# mcu.net
KiCad netlist of a schematic drawn in Altium Designer
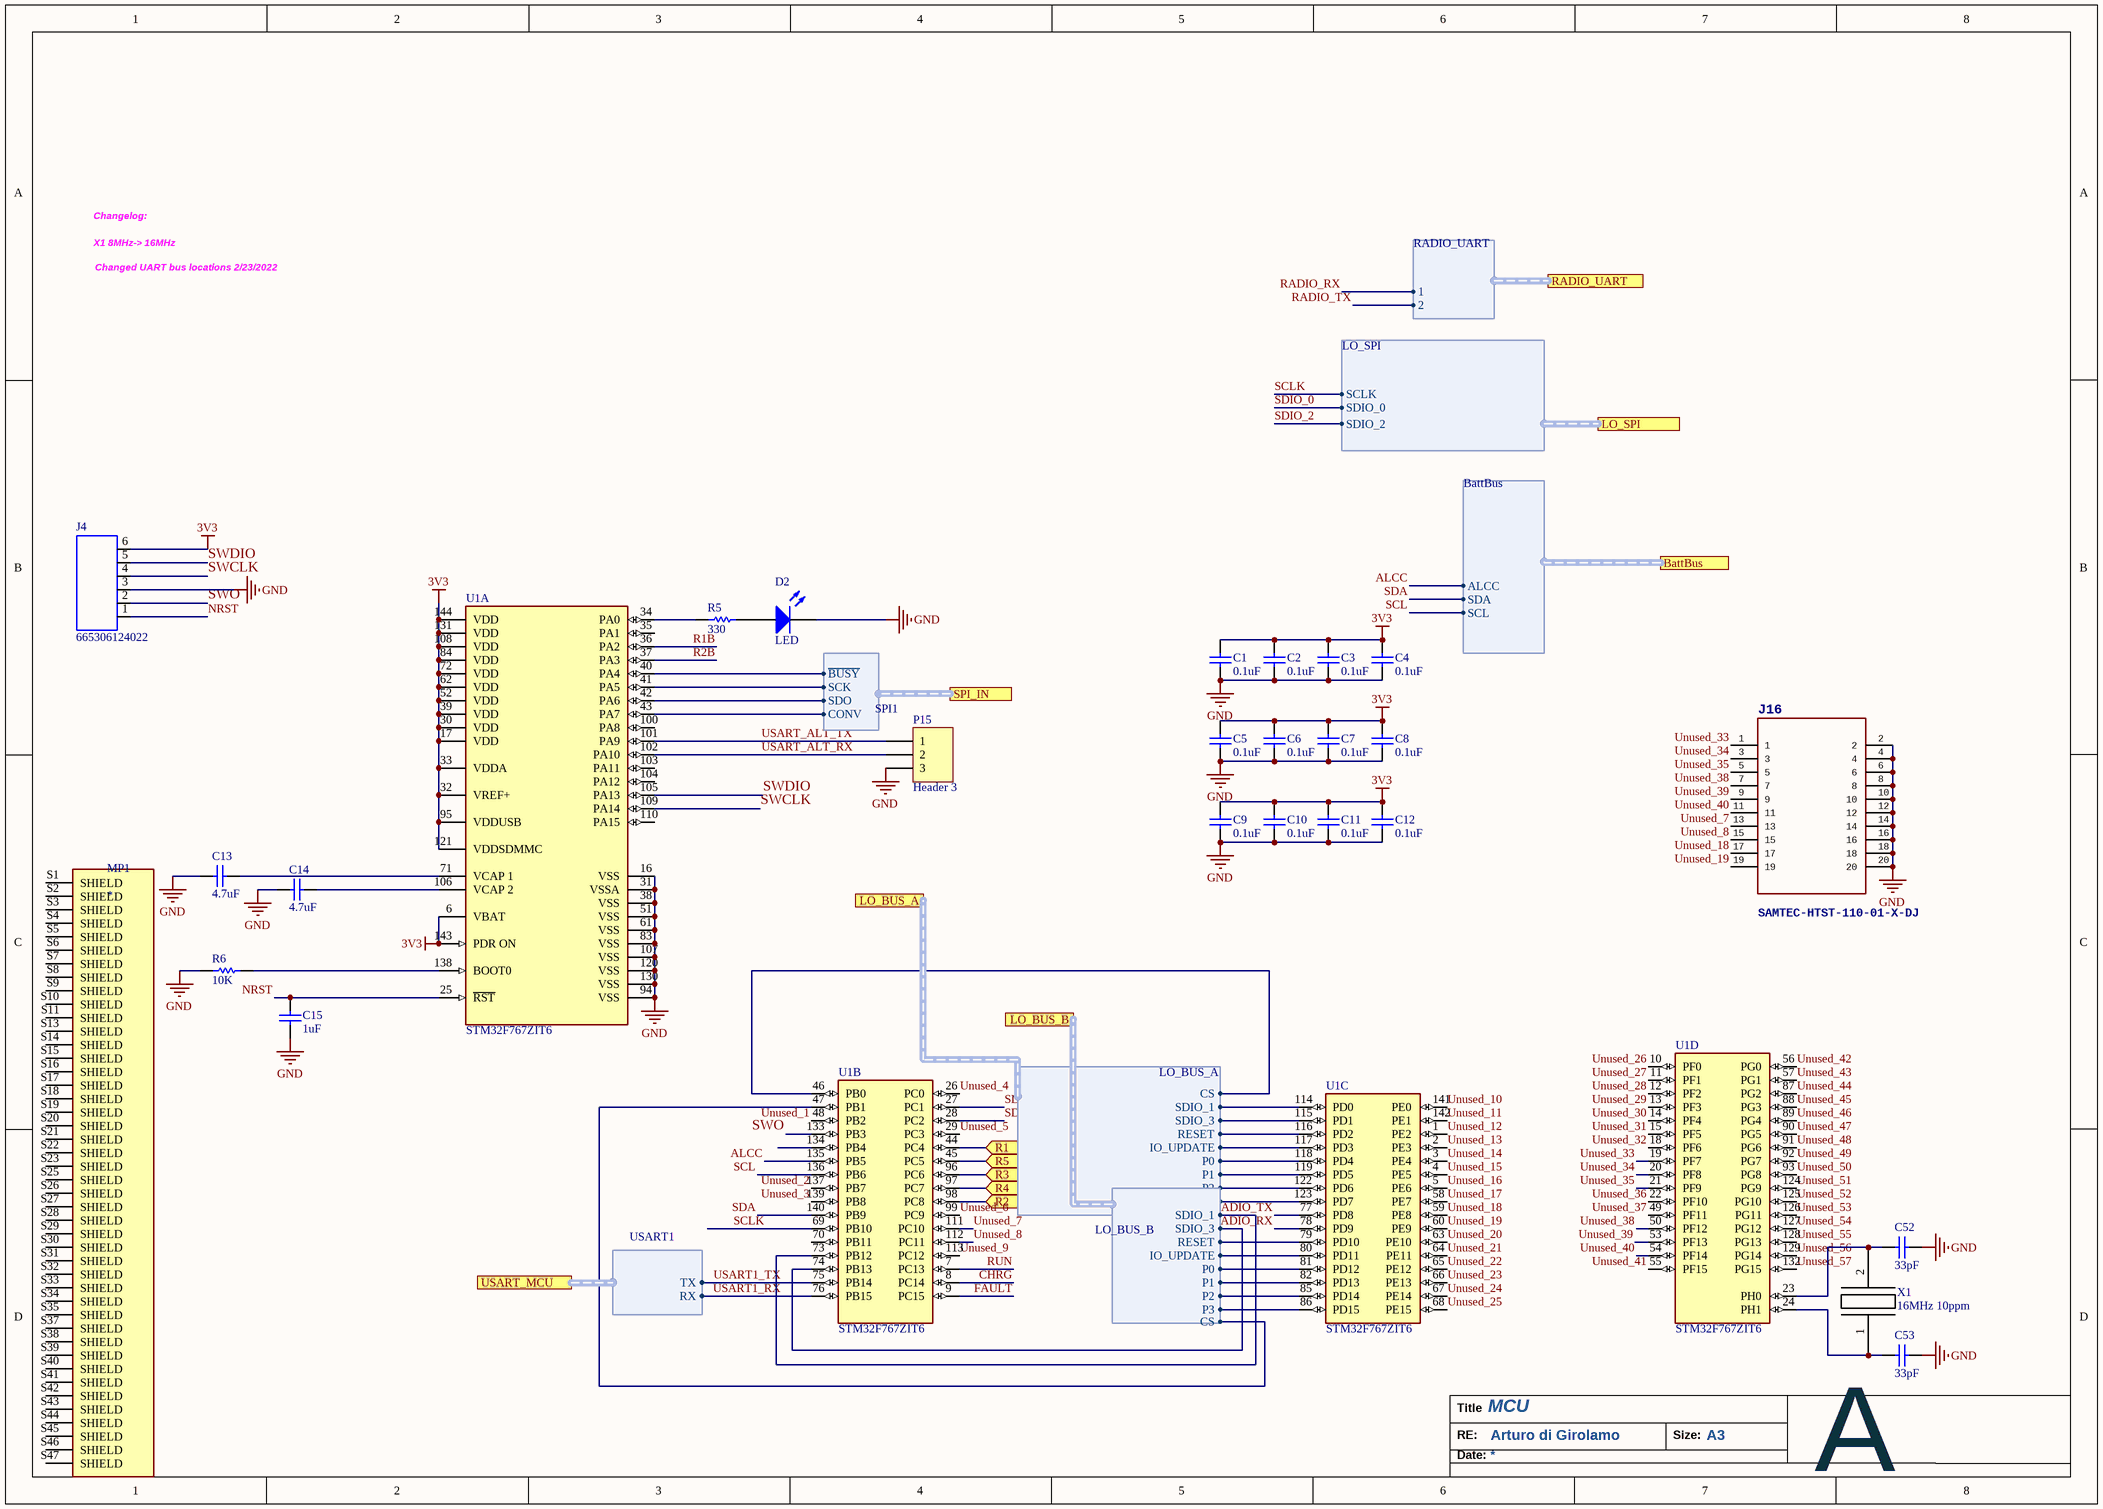
[diagram p0: mcu.SchDoc]

(export (version "E")
  (design (tool "Eeschema 10.0.6"))
  (components
    (comp (ref "C1")
      (value "0.1uF")
      (footprint "0402_Cap")
      (description "Capacitor, 0.1uF, 0805")
      (libsource (lib "Arturo_Approved") (part "CL21B104KACNNNC"))
    )
    (comp (ref "C2")
      (value "0.1uF")
      (footprint "0402_Cap")
      (description "Capacitor, 0.1uF, 0805")
      (libsource (lib "Arturo_Approved") (part "CL21B104KACNNNC"))
    )
    (comp (ref "C3")
      (value "0.1uF")
      (footprint "0402_Cap")
      (description "Capacitor, 0.1uF, 0805")
      (libsource (lib "Arturo_Approved") (part "CL21B104KACNNNC"))
    )
    (comp (ref "C4")
      (value "0.1uF")
      (footprint "0402_Cap")
      (description "Capacitor, 0.1uF, 0805")
      (libsource (lib "Arturo_Approved") (part "CL21B104KACNNNC"))
    )
    (comp (ref "C5")
      (value "0.1uF")
      (footprint "0402_Cap")
      (description "Capacitor, 0.1uF, 0805")
      (libsource (lib "Arturo_Approved") (part "CL21B104KACNNNC"))
    )
    (comp (ref "C6")
      (value "0.1uF")
      (footprint "0402_Cap")
      (description "Capacitor, 0.1uF, 0805")
      (libsource (lib "Arturo_Approved") (part "CL21B104KACNNNC"))
    )
    (comp (ref "C7")
      (value "0.1uF")
      (footprint "0402_Cap")
      (description "Capacitor, 0.1uF, 0805")
      (libsource (lib "Arturo_Approved") (part "CL21B104KACNNNC"))
    )
    (comp (ref "C8")
      (value "0.1uF")
      (footprint "0402_Cap")
      (description "Capacitor, 0.1uF, 0805")
      (libsource (lib "Arturo_Approved") (part "CL21B104KACNNNC"))
    )
    (comp (ref "C9")
      (value "0.1uF")
      (footprint "0402_Cap")
      (description "Capacitor, 0.1uF, 0805")
      (libsource (lib "Arturo_Approved") (part "CL21B104KACNNNC"))
    )
    (comp (ref "C10")
      (value "0.1uF")
      (footprint "0402_Cap")
      (description "Capacitor, 0.1uF, 0805")
      (libsource (lib "Arturo_Approved") (part "CL21B104KACNNNC"))
    )
    (comp (ref "C11")
      (value "0.1uF")
      (footprint "0402_Cap")
      (description "Capacitor, 0.1uF, 0805")
      (libsource (lib "Arturo_Approved") (part "CL21B104KACNNNC"))
    )
    (comp (ref "C12")
      (value "0.1uF")
      (footprint "0402_Cap")
      (description "Capacitor, 0.1uF, 0805")
      (libsource (lib "Arturo_Approved") (part "CL21B104KACNNNC"))
    )
    (comp (ref "C13")
      (value "4.7uF")
      (footprint "0402_Cap")
      (description "Capacitor, 4.7uF, 0805")
      (libsource (lib "Arturo_Approved") (part "CL21A475KAQNNNE"))
    )
    (comp (ref "C14")
      (value "4.7uF")
      (footprint "0402_Cap")
      (description "Capacitor, 4.7uF, 0805")
      (libsource (lib "Arturo_Approved") (part "CL21A475KAQNNNE"))
    )
    (comp (ref "C15")
      (value "1uF")
      (footprint "0402_Cap")
      (description "Capacitor, 1uF, 0805")
      (libsource (lib "Arturo_Approved") (part "CL21B105KBFNFNE"))
    )
    (comp (ref "C52")
      (value "33pF")
      (footprint "0402_Cap")
      (description "Capacitor, 33pF, 0805")
      (libsource (lib "Arturo_Approved") (part "CC0805GRNPO9BN330"))
    )
    (comp (ref "C53")
      (value "33pF")
      (footprint "0402_Cap")
      (description "Capacitor, 33pF, 0805")
      (libsource (lib "Arturo_Approved") (part "CC0805GRNPO9BN330"))
    )
    (comp (ref "D2")
      (value "LED")
      (footprint "STD_LED")
      (description "Typical LED")
      (libsource (lib "Arturo_Approved") (part "LNJ037X8ARA"))
    )
    (comp (ref "J4")
      (value "665306124022")
      (footprint "6pin_we")
      (description "Connector Header Surface Mount 6 position 0.039 (1.00mm)")
      (fields (field (name "MF") "WÃ¼rth Elektronik"))
      (libsource (lib "Arturo_Approved") (part "6pin_WE"))
    )
    (comp (ref "J16")
      (value "SAMTEC-HTST-110-01-X-DJ")
      (footprint "SAMTEC-HTST-110-01-X-D")
      (libsource (lib "Arturo_Approved") (part "SAMTEC-HTST-110-01-X-DJ"))
    )
    (comp (ref "MP1")
      (value "*")
      (footprint "WURTH_36103605S")
      (description "RF SHIELD 2.362\" SURFACE MOUNT")
      (fields (field (name "MP") "36103605S"))
      (libsource (lib "*") (part "36103605S"))
    )
    (comp (ref "P15")
      (value "Header 3")
      (footprint "HDR1X3")
      (description "Header, 3-Pin")
      (fields (field (name "PUBLISHER") "Altium Limited"))
      (libsource (lib "Miscellaneous Connectors") (part "Header 3"))
    )
    (comp (ref "R5")
      (value "330")
      (footprint "0402_Res")
      (description "330 1% 1/3W")
      (libsource (lib "Arturo_Approved") (part "RL1220S-R33-F"))
    )
    (comp (ref "R6")
      (value "10K")
      (footprint "0402_Res")
      (description "10K 1% 1/4W")
      (libsource (lib "Arturo_Approved") (part "RNCP0805FTD10K0"))
    )
    (comp (ref "U1")
      (value "STM32F767ZIT6")
      (footprint "FP-LQFP144-1A-MFG")
      (description "IC MCU 32BIT 2MB FLASH 144LQFP")
      (fields
        (field (name "OCTOPART") "https://octopart.com/stm32f767zit6-stmicroelectronics-70527068")
        (field (name "MANUFACTURER") "STMicroelectronics")
      )
      (libsource (lib "Altium Content Vault") (part "5045e889cff10565096e715f5715cbd"))
    )
    (comp (ref "X1")
      (value "16MHz 10ppm")
      (footprint "XTAL_ECS-160-20-4X")
      (libsource (lib "Arturo_Approved") (part "9B-8.000MEEJ-B"))
    )
  )
  (nets
    (net (code "8") (name "/ALCC") (class "Default")
      (node (ref "U1") (pin "135") (pinfunction "PB5_135") (pintype "bidirectional"))
    )
    (net (code "9") (name "/CHRG") (class "Default")
      (node (ref "U1") (pin "8") (pinfunction "PC14_8") (pintype "bidirectional"))
    )
    (net (code "10") (name "/CONV") (class "Default")
      (node (ref "U1") (pin "43") (pinfunction "PA7_43") (pintype "bidirectional"))
    )
    (net (code "11") (name "/FAULT") (class "Default")
      (node (ref "U1") (pin "9") (pinfunction "PC15_9") (pintype "bidirectional"))
    )
    (net (code "13") (name "/NRST") (class "Default")
      (node (ref "C15") (pin "2") (pinfunction "2_2") (pintype "passive"))
      (node (ref "J4") (pin "1") (pinfunction "1_1") (pintype "passive"))
      (node (ref "U1") (pin "25") (pinfunction "~{RST}_25") (pintype "input"))
    )
    (net (code "14") (name "/R1") (class "Default")
      (node (ref "U1") (pin "44") (pinfunction "PC4_44") (pintype "bidirectional"))
    )
    (net (code "15") (name "/R1B") (class "Default")
      (node (ref "U1") (pin "36") (pinfunction "PA2_36") (pintype "bidirectional"))
    )
    (net (code "16") (name "/R2") (class "Default")
      (node (ref "U1") (pin "98") (pinfunction "PC8_98") (pintype "bidirectional"))
    )
    (net (code "17") (name "/R2B") (class "Default")
      (node (ref "U1") (pin "37") (pinfunction "PA3_37") (pintype "bidirectional"))
    )
    (net (code "18") (name "/R3") (class "Default")
      (node (ref "U1") (pin "96") (pinfunction "PC6_96") (pintype "bidirectional"))
    )
    (net (code "19") (name "/R4") (class "Default")
      (node (ref "U1") (pin "97") (pinfunction "PC7_97") (pintype "bidirectional"))
    )
    (net (code "20") (name "/R5") (class "Default")
      (node (ref "U1") (pin "45") (pinfunction "PC5_45") (pintype "bidirectional"))
    )
    (net (code "21") (name "/RADIO_RX") (class "Default")
      (node (ref "U1") (pin "78") (pinfunction "PD9_78") (pintype "bidirectional"))
    )
    (net (code "22") (name "/RADIO_TX") (class "Default")
      (node (ref "U1") (pin "77") (pinfunction "PD8_77") (pintype "bidirectional"))
    )
    (net (code "23") (name "/RUN") (class "Default")
      (node (ref "U1") (pin "7") (pinfunction "PC13_7") (pintype "bidirectional"))
    )
    (net (code "24") (name "/SCK") (class "Default")
      (node (ref "U1") (pin "41") (pinfunction "PA5_41") (pintype "bidirectional"))
    )
    (net (code "25") (name "/SCL") (class "Default")
      (node (ref "U1") (pin "136") (pinfunction "PB6_136") (pintype "bidirectional"))
    )
    (net (code "26") (name "/SCLK") (class "Default")
      (node (ref "U1") (pin "69") (pinfunction "PB10_69") (pintype "bidirectional"))
    )
    (net (code "27") (name "/SDA") (class "Default")
      (node (ref "U1") (pin "140") (pinfunction "PB9_140") (pintype "bidirectional"))
    )
    (net (code "28") (name "/SDIO_0") (class "Default")
      (node (ref "U1") (pin "27") (pinfunction "PC1_27") (pintype "bidirectional"))
    )
    (net (code "29") (name "/SDIO_2") (class "Default")
      (node (ref "U1") (pin "28") (pinfunction "PC2_28") (pintype "bidirectional"))
    )
    (net (code "30") (name "/SDO") (class "Default")
      (node (ref "U1") (pin "42") (pinfunction "PA6_42") (pintype "bidirectional"))
    )
    (net (code "31") (name "/SWCLK") (class "Default")
      (node (ref "J4") (pin "4") (pinfunction "4_4") (pintype "passive"))
      (node (ref "U1") (pin "109") (pinfunction "PA14_109") (pintype "bidirectional"))
    )
    (net (code "32") (name "/SWDIO") (class "Default")
      (node (ref "J4") (pin "5") (pinfunction "5_5") (pintype "passive"))
      (node (ref "U1") (pin "105") (pinfunction "PA13_105") (pintype "bidirectional"))
    )
    (net (code "33") (name "/SWO") (class "Default")
      (node (ref "J4") (pin "2") (pinfunction "2_2") (pintype "passive"))
      (node (ref "U1") (pin "133") (pinfunction "PB3_133") (pintype "bidirectional"))
    )
    (net (code "34") (name "/USART1_RX") (class "Default")
      (node (ref "U1") (pin "76") (pinfunction "PB15_76") (pintype "bidirectional"))
    )
    (net (code "35") (name "/USART1_TX") (class "Default")
      (node (ref "U1") (pin "75") (pinfunction "PB14_75") (pintype "bidirectional"))
    )
    (net (code "36") (name "/USART_ALT_RX") (class "Default")
      (node (ref "P15") (pin "2") (pinfunction "2_2") (pintype "passive"))
      (node (ref "U1") (pin "102") (pinfunction "PA10_102") (pintype "bidirectional"))
    )
    (net (code "37") (name "/USART_ALT_TX") (class "Default")
      (node (ref "P15") (pin "1") (pinfunction "1_1") (pintype "passive"))
      (node (ref "U1") (pin "101") (pinfunction "PA9_101") (pintype "bidirectional"))
    )
    (net (code "38") (name "/Unused_1") (class "Default")
      (node (ref "U1") (pin "48") (pinfunction "PB2_48") (pintype "bidirectional"))
    )
    (net (code "39") (name "/Unused_2") (class "Default")
      (node (ref "U1") (pin "137") (pinfunction "PB7_137") (pintype "bidirectional"))
    )
    (net (code "40") (name "/Unused_3") (class "Default")
      (node (ref "U1") (pin "139") (pinfunction "PB8_139") (pintype "bidirectional"))
    )
    (net (code "41") (name "/Unused_4") (class "Default")
      (node (ref "U1") (pin "26") (pinfunction "PC0_26") (pintype "bidirectional"))
    )
    (net (code "42") (name "/Unused_5") (class "Default")
      (node (ref "U1") (pin "29") (pinfunction "PC3_29") (pintype "bidirectional"))
    )
    (net (code "43") (name "/Unused_6") (class "Default")
      (node (ref "U1") (pin "99") (pinfunction "PC9_99") (pintype "bidirectional"))
    )
    (net (code "44") (name "/Unused_7") (class "Default")
      (node (ref "J16") (pin "13") (pinfunction "13_13") (pintype "passive"))
      (node (ref "U1") (pin "111") (pinfunction "PC10_111") (pintype "bidirectional"))
    )
    (net (code "45") (name "/Unused_8") (class "Default")
      (node (ref "J16") (pin "15") (pinfunction "15_15") (pintype "passive"))
      (node (ref "U1") (pin "112") (pinfunction "PC11_112") (pintype "bidirectional"))
    )
    (net (code "46") (name "/Unused_9") (class "Default")
      (node (ref "U1") (pin "113") (pinfunction "PC12_113") (pintype "bidirectional"))
    )
    (net (code "47") (name "/Unused_10") (class "Default")
      (node (ref "U1") (pin "141") (pinfunction "PE0_141") (pintype "bidirectional"))
    )
    (net (code "48") (name "/Unused_11") (class "Default")
      (node (ref "U1") (pin "142") (pinfunction "PE1_142") (pintype "bidirectional"))
    )
    (net (code "49") (name "/Unused_12") (class "Default")
      (node (ref "U1") (pin "1") (pinfunction "PE2_1") (pintype "bidirectional"))
    )
    (net (code "50") (name "/Unused_13") (class "Default")
      (node (ref "U1") (pin "2") (pinfunction "PE3_2") (pintype "bidirectional"))
    )
    (net (code "51") (name "/Unused_14") (class "Default")
      (node (ref "U1") (pin "3") (pinfunction "PE4_3") (pintype "bidirectional"))
    )
    (net (code "52") (name "/Unused_15") (class "Default")
      (node (ref "U1") (pin "4") (pinfunction "PE5_4") (pintype "bidirectional"))
    )
    (net (code "53") (name "/Unused_16") (class "Default")
      (node (ref "U1") (pin "5") (pinfunction "PE6_5") (pintype "bidirectional"))
    )
    (net (code "54") (name "/Unused_17") (class "Default")
      (node (ref "U1") (pin "58") (pinfunction "PE7_58") (pintype "bidirectional"))
    )
    (net (code "55") (name "/Unused_18") (class "Default")
      (node (ref "J16") (pin "17") (pinfunction "17_17") (pintype "passive"))
      (node (ref "U1") (pin "59") (pinfunction "PE8_59") (pintype "bidirectional"))
    )
    (net (code "56") (name "/Unused_19") (class "Default")
      (node (ref "J16") (pin "19") (pinfunction "19_19") (pintype "passive"))
      (node (ref "U1") (pin "60") (pinfunction "PE9_60") (pintype "bidirectional"))
    )
    (net (code "57") (name "/Unused_20") (class "Default")
      (node (ref "U1") (pin "63") (pinfunction "PE10_63") (pintype "bidirectional"))
    )
    (net (code "58") (name "/Unused_21") (class "Default")
      (node (ref "U1") (pin "64") (pinfunction "PE11_64") (pintype "bidirectional"))
    )
    (net (code "59") (name "/Unused_22") (class "Default")
      (node (ref "U1") (pin "65") (pinfunction "PE12_65") (pintype "bidirectional"))
    )
    (net (code "60") (name "/Unused_23") (class "Default")
      (node (ref "U1") (pin "66") (pinfunction "PE13_66") (pintype "bidirectional"))
    )
    (net (code "61") (name "/Unused_24") (class "Default")
      (node (ref "U1") (pin "67") (pinfunction "PE14_67") (pintype "bidirectional"))
    )
    (net (code "62") (name "/Unused_25") (class "Default")
      (node (ref "U1") (pin "68") (pinfunction "PE15_68") (pintype "bidirectional"))
    )
    (net (code "63") (name "/Unused_26") (class "Default")
      (node (ref "U1") (pin "10") (pinfunction "PF0_10") (pintype "bidirectional"))
    )
    (net (code "64") (name "/Unused_27") (class "Default")
      (node (ref "U1") (pin "11") (pinfunction "PF1_11") (pintype "bidirectional"))
    )
    (net (code "65") (name "/Unused_28") (class "Default")
      (node (ref "U1") (pin "12") (pinfunction "PF2_12") (pintype "bidirectional"))
    )
    (net (code "66") (name "/Unused_29") (class "Default")
      (node (ref "U1") (pin "13") (pinfunction "PF3_13") (pintype "bidirectional"))
    )
    (net (code "67") (name "/Unused_30") (class "Default")
      (node (ref "U1") (pin "14") (pinfunction "PF4_14") (pintype "bidirectional"))
    )
    (net (code "68") (name "/Unused_31") (class "Default")
      (node (ref "U1") (pin "15") (pinfunction "PF5_15") (pintype "bidirectional"))
    )
    (net (code "69") (name "/Unused_32") (class "Default")
      (node (ref "U1") (pin "18") (pinfunction "PF6_18") (pintype "bidirectional"))
    )
    (net (code "70") (name "/Unused_33") (class "Default")
      (node (ref "J16") (pin "1") (pinfunction "1_1") (pintype "passive"))
      (node (ref "U1") (pin "19") (pinfunction "PF7_19") (pintype "bidirectional"))
    )
    (net (code "71") (name "/Unused_34") (class "Default")
      (node (ref "J16") (pin "3") (pinfunction "3_3") (pintype "passive"))
      (node (ref "U1") (pin "20") (pinfunction "PF8_20") (pintype "bidirectional"))
    )
    (net (code "72") (name "/Unused_35") (class "Default")
      (node (ref "J16") (pin "5") (pinfunction "5_5") (pintype "passive"))
      (node (ref "U1") (pin "21") (pinfunction "PF9_21") (pintype "bidirectional"))
    )
    (net (code "73") (name "/Unused_36") (class "Default")
      (node (ref "U1") (pin "22") (pinfunction "PF10_22") (pintype "bidirectional"))
    )
    (net (code "74") (name "/Unused_37") (class "Default")
      (node (ref "U1") (pin "49") (pinfunction "PF11_49") (pintype "bidirectional"))
    )
    (net (code "75") (name "/Unused_38") (class "Default")
      (node (ref "J16") (pin "7") (pinfunction "7_7") (pintype "passive"))
      (node (ref "U1") (pin "50") (pinfunction "PF12_50") (pintype "bidirectional"))
    )
    (net (code "76") (name "/Unused_39") (class "Default")
      (node (ref "J16") (pin "9") (pinfunction "9_9") (pintype "passive"))
      (node (ref "U1") (pin "53") (pinfunction "PF13_53") (pintype "bidirectional"))
    )
    (net (code "77") (name "/Unused_40") (class "Default")
      (node (ref "J16") (pin "11") (pinfunction "11_11") (pintype "passive"))
      (node (ref "U1") (pin "54") (pinfunction "PF14_54") (pintype "bidirectional"))
    )
    (net (code "78") (name "/Unused_41") (class "Default")
      (node (ref "U1") (pin "55") (pinfunction "PF15_55") (pintype "bidirectional"))
    )
    (net (code "79") (name "/Unused_42") (class "Default")
      (node (ref "U1") (pin "56") (pinfunction "PG0_56") (pintype "bidirectional"))
    )
    (net (code "80") (name "/Unused_43") (class "Default")
      (node (ref "U1") (pin "57") (pinfunction "PG1_57") (pintype "bidirectional"))
    )
    (net (code "81") (name "/Unused_44") (class "Default")
      (node (ref "U1") (pin "87") (pinfunction "PG2_87") (pintype "bidirectional"))
    )
    (net (code "82") (name "/Unused_45") (class "Default")
      (node (ref "U1") (pin "88") (pinfunction "PG3_88") (pintype "bidirectional"))
    )
    (net (code "83") (name "/Unused_46") (class "Default")
      (node (ref "U1") (pin "89") (pinfunction "PG4_89") (pintype "bidirectional"))
    )
    (net (code "84") (name "/Unused_47") (class "Default")
      (node (ref "U1") (pin "90") (pinfunction "PG5_90") (pintype "bidirectional"))
    )
    (net (code "85") (name "/Unused_48") (class "Default")
      (node (ref "U1") (pin "91") (pinfunction "PG6_91") (pintype "bidirectional"))
    )
    (net (code "86") (name "/Unused_49") (class "Default")
      (node (ref "U1") (pin "92") (pinfunction "PG7_92") (pintype "bidirectional"))
    )
    (net (code "87") (name "/Unused_50") (class "Default")
      (node (ref "U1") (pin "93") (pinfunction "PG8_93") (pintype "bidirectional"))
    )
    (net (code "88") (name "/Unused_51") (class "Default")
      (node (ref "U1") (pin "124") (pinfunction "PG9_124") (pintype "bidirectional"))
    )
    (net (code "89") (name "/Unused_52") (class "Default")
      (node (ref "U1") (pin "125") (pinfunction "PG10_125") (pintype "bidirectional"))
    )
    (net (code "90") (name "/Unused_53") (class "Default")
      (node (ref "U1") (pin "126") (pinfunction "PG11_126") (pintype "bidirectional"))
    )
    (net (code "91") (name "/Unused_54") (class "Default")
      (node (ref "U1") (pin "127") (pinfunction "PG12_127") (pintype "bidirectional"))
    )
    (net (code "92") (name "/Unused_55") (class "Default")
      (node (ref "U1") (pin "128") (pinfunction "PG13_128") (pintype "bidirectional"))
    )
    (net (code "93") (name "/Unused_56") (class "Default")
      (node (ref "U1") (pin "129") (pinfunction "PG14_129") (pintype "bidirectional"))
    )
    (net (code "94") (name "/Unused_57") (class "Default")
      (node (ref "U1") (pin "132") (pinfunction "PG15_132") (pintype "bidirectional"))
    )
    (net (code "101") (name "/~{BUSY}") (class "Default")
      (node (ref "U1") (pin "40") (pinfunction "PA4_40") (pintype "bidirectional"))
    )
    (net (code "102") (name "3V3") (class "Default")
      (node (ref "C1") (pin "2") (pinfunction "2_2") (pintype "passive"))
      (node (ref "C10") (pin "2") (pinfunction "2_2") (pintype "passive"))
      (node (ref "C11") (pin "2") (pinfunction "2_2") (pintype "passive"))
      (node (ref "C12") (pin "2") (pinfunction "2_2") (pintype "passive"))
      (node (ref "C2") (pin "2") (pinfunction "2_2") (pintype "passive"))
      (node (ref "C3") (pin "2") (pinfunction "2_2") (pintype "passive"))
      (node (ref "C4") (pin "2") (pinfunction "2_2") (pintype "passive"))
      (node (ref "C5") (pin "2") (pinfunction "2_2") (pintype "passive"))
      (node (ref "C6") (pin "2") (pinfunction "2_2") (pintype "passive"))
      (node (ref "C7") (pin "2") (pinfunction "2_2") (pintype "passive"))
      (node (ref "C8") (pin "2") (pinfunction "2_2") (pintype "passive"))
      (node (ref "C9") (pin "2") (pinfunction "2_2") (pintype "passive"))
      (node (ref "J4") (pin "6") (pinfunction "6_6") (pintype "passive"))
      (node (ref "U1") (pin "108") (pinfunction "VDD_108") (pintype "power_in"))
      (node (ref "U1") (pin "121") (pinfunction "VDDSDMMC_121") (pintype "power_in"))
      (node (ref "U1") (pin "131") (pinfunction "VDD_131") (pintype "power_in"))
      (node (ref "U1") (pin "143") (pinfunction "PDR_ON_143") (pintype "input"))
      (node (ref "U1") (pin "144") (pinfunction "VDD_144") (pintype "power_in"))
      (node (ref "U1") (pin "17") (pinfunction "VDD_17") (pintype "power_in"))
      (node (ref "U1") (pin "30") (pinfunction "VDD_30") (pintype "power_in"))
      (node (ref "U1") (pin "32") (pinfunction "VREF+_32") (pintype "power_in"))
      (node (ref "U1") (pin "33") (pinfunction "VDDA_33") (pintype "power_in"))
      (node (ref "U1") (pin "39") (pinfunction "VDD_39") (pintype "power_in"))
      (node (ref "U1") (pin "52") (pinfunction "VDD_52") (pintype "power_in"))
      (node (ref "U1") (pin "6") (pinfunction "VBAT_6") (pintype "power_in"))
      (node (ref "U1") (pin "62") (pinfunction "VDD_62") (pintype "power_in"))
      (node (ref "U1") (pin "72") (pinfunction "VDD_72") (pintype "power_in"))
      (node (ref "U1") (pin "84") (pinfunction "VDD_84") (pintype "power_in"))
      (node (ref "U1") (pin "95") (pinfunction "VDDUSB_95") (pintype "power_in"))
    )
    (net (code "103") (name "GND") (class "Default")
      (node (ref "C1") (pin "1") (pinfunction "1_1") (pintype "passive"))
      (node (ref "C10") (pin "1") (pinfunction "1_1") (pintype "passive"))
      (node (ref "C11") (pin "1") (pinfunction "1_1") (pintype "passive"))
      (node (ref "C12") (pin "1") (pinfunction "1_1") (pintype "passive"))
      (node (ref "C13") (pin "1") (pinfunction "1_1") (pintype "passive"))
      (node (ref "C14") (pin "1") (pinfunction "1_1") (pintype "passive"))
      (node (ref "C15") (pin "1") (pinfunction "1_1") (pintype "passive"))
      (node (ref "C2") (pin "1") (pinfunction "1_1") (pintype "passive"))
      (node (ref "C3") (pin "1") (pinfunction "1_1") (pintype "passive"))
      (node (ref "C4") (pin "1") (pinfunction "1_1") (pintype "passive"))
      (node (ref "C5") (pin "1") (pinfunction "1_1") (pintype "passive"))
      (node (ref "C52") (pin "2") (pinfunction "2_2") (pintype "passive"))
      (node (ref "C53") (pin "2") (pinfunction "2_2") (pintype "passive"))
      (node (ref "C6") (pin "1") (pinfunction "1_1") (pintype "passive"))
      (node (ref "C7") (pin "1") (pinfunction "1_1") (pintype "passive"))
      (node (ref "C8") (pin "1") (pinfunction "1_1") (pintype "passive"))
      (node (ref "C9") (pin "1") (pinfunction "1_1") (pintype "passive"))
      (node (ref "D2") (pin "2") (pinfunction "2_2") (pintype "passive"))
      (node (ref "J16") (pin "10") (pinfunction "10_10") (pintype "passive"))
      (node (ref "J16") (pin "12") (pinfunction "12_12") (pintype "passive"))
      (node (ref "J16") (pin "14") (pinfunction "14_14") (pintype "passive"))
      (node (ref "J16") (pin "16") (pinfunction "16_16") (pintype "passive"))
      (node (ref "J16") (pin "18") (pinfunction "18_18") (pintype "passive"))
      (node (ref "J16") (pin "2") (pinfunction "2_2") (pintype "passive"))
      (node (ref "J16") (pin "20") (pinfunction "20_20") (pintype "passive"))
      (node (ref "J16") (pin "4") (pinfunction "4_4") (pintype "passive"))
      (node (ref "J16") (pin "6") (pinfunction "6_6") (pintype "passive"))
      (node (ref "J16") (pin "8") (pinfunction "8_8") (pintype "passive"))
      (node (ref "J4") (pin "3") (pinfunction "3_3") (pintype "passive"))
      (node (ref "P15") (pin "3") (pinfunction "3_3") (pintype "passive"))
      (node (ref "R6") (pin "1") (pinfunction "1_1") (pintype "passive"))
      (node (ref "U1") (pin "107") (pinfunction "VSS_107") (pintype "power_in"))
      (node (ref "U1") (pin "120") (pinfunction "VSS_120") (pintype "power_in"))
      (node (ref "U1") (pin "130") (pinfunction "VSS_130") (pintype "power_in"))
      (node (ref "U1") (pin "16") (pinfunction "VSS_16") (pintype "power_in"))
      (node (ref "U1") (pin "31") (pinfunction "VSSA_31") (pintype "power_in"))
      (node (ref "U1") (pin "38") (pinfunction "VSS_38") (pintype "power_in"))
      (node (ref "U1") (pin "51") (pinfunction "VSS_51") (pintype "power_in"))
      (node (ref "U1") (pin "61") (pinfunction "VSS_61") (pintype "power_in"))
      (node (ref "U1") (pin "83") (pinfunction "VSS_83") (pintype "power_in"))
      (node (ref "U1") (pin "94") (pinfunction "VSS_94") (pintype "power_in"))
    )
    (net (code "104") (name "Net-(D2-Pad1)") (class "Default")
      (node (ref "D2") (pin "1") (pinfunction "1_1") (pintype "passive"))
      (node (ref "R5") (pin "2") (pinfunction "2_2") (pintype "passive"))
    )
    (net (code "105") (name "Net-(U1A-BOOT0)") (class "Default")
      (node (ref "R6") (pin "2") (pinfunction "2_2") (pintype "passive"))
      (node (ref "U1") (pin "138") (pinfunction "BOOT0_138") (pintype "input"))
    )
    (net (code "106") (name "Net-(U1A-PA0)") (class "Default")
      (node (ref "R5") (pin "1") (pinfunction "1_1") (pintype "passive"))
      (node (ref "U1") (pin "34") (pinfunction "PA0_34") (pintype "bidirectional"))
    )
    (net (code "107") (name "Net-(U1A-VCAP_1)") (class "Default")
      (node (ref "C13") (pin "2") (pinfunction "2_2") (pintype "passive"))
      (node (ref "U1") (pin "71") (pinfunction "VCAP_1_71") (pintype "power_in"))
    )
    (net (code "108") (name "Net-(U1A-VCAP_2)") (class "Default")
      (node (ref "C14") (pin "2") (pinfunction "2_2") (pintype "passive"))
      (node (ref "U1") (pin "106") (pinfunction "VCAP_2_106") (pintype "power_in"))
    )
    (net (code "109") (name "Net-(U1D-PH0)") (class "Default")
      (node (ref "C52") (pin "1") (pinfunction "1_1") (pintype "passive"))
      (node (ref "U1") (pin "23") (pinfunction "PH0_23") (pintype "bidirectional"))
      (node (ref "X1") (pin "2") (pinfunction "2_2") (pintype "passive"))
    )
    (net (code "110") (name "Net-(U1D-PH1)") (class "Default")
      (node (ref "C53") (pin "1") (pinfunction "1_1") (pintype "passive"))
      (node (ref "U1") (pin "24") (pinfunction "PH1_24") (pintype "bidirectional"))
      (node (ref "X1") (pin "1") (pinfunction "1_1") (pintype "passive"))
    )
    (net (code "111") (name "unconnected-(MP1-SHIELD-PadS1)") (class "Default")
      (node (ref "MP1") (pin "S1") (pinfunction "SHIELD_S1") (pintype "passive"))
    )
    (net (code "112") (name "unconnected-(MP1-SHIELD-PadS2)") (class "Default")
      (node (ref "MP1") (pin "S2") (pinfunction "SHIELD_S2") (pintype "passive"))
    )
    (net (code "113") (name "unconnected-(MP1-SHIELD-PadS3)") (class "Default")
      (node (ref "MP1") (pin "S3") (pinfunction "SHIELD_S3") (pintype "passive"))
    )
    (net (code "114") (name "unconnected-(MP1-SHIELD-PadS4)") (class "Default")
      (node (ref "MP1") (pin "S4") (pinfunction "SHIELD_S4") (pintype "passive"))
    )
    (net (code "115") (name "unconnected-(MP1-SHIELD-PadS5)") (class "Default")
      (node (ref "MP1") (pin "S5") (pinfunction "SHIELD_S5") (pintype "passive"))
    )
    (net (code "116") (name "unconnected-(MP1-SHIELD-PadS6)") (class "Default")
      (node (ref "MP1") (pin "S6") (pinfunction "SHIELD_S6") (pintype "passive"))
    )
    (net (code "117") (name "unconnected-(MP1-SHIELD-PadS7)") (class "Default")
      (node (ref "MP1") (pin "S7") (pinfunction "SHIELD_S7") (pintype "passive"))
    )
    (net (code "118") (name "unconnected-(MP1-SHIELD-PadS8)") (class "Default")
      (node (ref "MP1") (pin "S8") (pinfunction "SHIELD_S8") (pintype "passive"))
    )
    (net (code "119") (name "unconnected-(MP1-SHIELD-PadS9)") (class "Default")
      (node (ref "MP1") (pin "S9") (pinfunction "SHIELD_S9") (pintype "passive"))
    )
    (net (code "120") (name "unconnected-(MP1-SHIELD-PadS10)") (class "Default")
      (node (ref "MP1") (pin "S10") (pinfunction "SHIELD_S10") (pintype "passive"))
    )
    (net (code "121") (name "unconnected-(MP1-SHIELD-PadS11)") (class "Default")
      (node (ref "MP1") (pin "S11") (pinfunction "SHIELD_S11") (pintype "passive"))
    )
    (net (code "122") (name "unconnected-(MP1-SHIELD-PadS13)") (class "Default")
      (node (ref "MP1") (pin "S13") (pinfunction "SHIELD_S13") (pintype "passive"))
    )
    (net (code "123") (name "unconnected-(MP1-SHIELD-PadS14)") (class "Default")
      (node (ref "MP1") (pin "S14") (pinfunction "SHIELD_S14") (pintype "passive"))
    )
    (net (code "124") (name "unconnected-(MP1-SHIELD-PadS15)") (class "Default")
      (node (ref "MP1") (pin "S15") (pinfunction "SHIELD_S15") (pintype "passive"))
    )
    (net (code "125") (name "unconnected-(MP1-SHIELD-PadS16)") (class "Default")
      (node (ref "MP1") (pin "S16") (pinfunction "SHIELD_S16") (pintype "passive"))
    )
    (net (code "126") (name "unconnected-(MP1-SHIELD-PadS17)") (class "Default")
      (node (ref "MP1") (pin "S17") (pinfunction "SHIELD_S17") (pintype "passive"))
    )
    (net (code "127") (name "unconnected-(MP1-SHIELD-PadS18)") (class "Default")
      (node (ref "MP1") (pin "S18") (pinfunction "SHIELD_S18") (pintype "passive"))
    )
    (net (code "128") (name "unconnected-(MP1-SHIELD-PadS19)") (class "Default")
      (node (ref "MP1") (pin "S19") (pinfunction "SHIELD_S19") (pintype "passive"))
    )
    (net (code "129") (name "unconnected-(MP1-SHIELD-PadS20)") (class "Default")
      (node (ref "MP1") (pin "S20") (pinfunction "SHIELD_S20") (pintype "passive"))
    )
    (net (code "130") (name "unconnected-(MP1-SHIELD-PadS21)") (class "Default")
      (node (ref "MP1") (pin "S21") (pinfunction "SHIELD_S21") (pintype "passive"))
    )
    (net (code "131") (name "unconnected-(MP1-SHIELD-PadS22)") (class "Default")
      (node (ref "MP1") (pin "S22") (pinfunction "SHIELD_S22") (pintype "passive"))
    )
    (net (code "132") (name "unconnected-(MP1-SHIELD-PadS23)") (class "Default")
      (node (ref "MP1") (pin "S23") (pinfunction "SHIELD_S23") (pintype "passive"))
    )
    (net (code "133") (name "unconnected-(MP1-SHIELD-PadS25)") (class "Default")
      (node (ref "MP1") (pin "S25") (pinfunction "SHIELD_S25") (pintype "passive"))
    )
    (net (code "134") (name "unconnected-(MP1-SHIELD-PadS26)") (class "Default")
      (node (ref "MP1") (pin "S26") (pinfunction "SHIELD_S26") (pintype "passive"))
    )
    (net (code "135") (name "unconnected-(MP1-SHIELD-PadS27)") (class "Default")
      (node (ref "MP1") (pin "S27") (pinfunction "SHIELD_S27") (pintype "passive"))
    )
    (net (code "136") (name "unconnected-(MP1-SHIELD-PadS28)") (class "Default")
      (node (ref "MP1") (pin "S28") (pinfunction "SHIELD_S28") (pintype "passive"))
    )
    (net (code "137") (name "unconnected-(MP1-SHIELD-PadS29)") (class "Default")
      (node (ref "MP1") (pin "S29") (pinfunction "SHIELD_S29") (pintype "passive"))
    )
    (net (code "138") (name "unconnected-(MP1-SHIELD-PadS30)") (class "Default")
      (node (ref "MP1") (pin "S30") (pinfunction "SHIELD_S30") (pintype "passive"))
    )
    (net (code "139") (name "unconnected-(MP1-SHIELD-PadS31)") (class "Default")
      (node (ref "MP1") (pin "S31") (pinfunction "SHIELD_S31") (pintype "passive"))
    )
    (net (code "140") (name "unconnected-(MP1-SHIELD-PadS32)") (class "Default")
      (node (ref "MP1") (pin "S32") (pinfunction "SHIELD_S32") (pintype "passive"))
    )
    (net (code "141") (name "unconnected-(MP1-SHIELD-PadS33)") (class "Default")
      (node (ref "MP1") (pin "S33") (pinfunction "SHIELD_S33") (pintype "passive"))
    )
    (net (code "142") (name "unconnected-(MP1-SHIELD-PadS34)") (class "Default")
      (node (ref "MP1") (pin "S34") (pinfunction "SHIELD_S34") (pintype "passive"))
    )
    (net (code "143") (name "unconnected-(MP1-SHIELD-PadS35)") (class "Default")
      (node (ref "MP1") (pin "S35") (pinfunction "SHIELD_S35") (pintype "passive"))
    )
    (net (code "144") (name "unconnected-(MP1-SHIELD-PadS37)") (class "Default")
      (node (ref "MP1") (pin "S37") (pinfunction "SHIELD_S37") (pintype "passive"))
    )
    (net (code "145") (name "unconnected-(MP1-SHIELD-PadS38)") (class "Default")
      (node (ref "MP1") (pin "S38") (pinfunction "SHIELD_S38") (pintype "passive"))
    )
    (net (code "146") (name "unconnected-(MP1-SHIELD-PadS39)") (class "Default")
      (node (ref "MP1") (pin "S39") (pinfunction "SHIELD_S39") (pintype "passive"))
    )
    (net (code "147") (name "unconnected-(MP1-SHIELD-PadS40)") (class "Default")
      (node (ref "MP1") (pin "S40") (pinfunction "SHIELD_S40") (pintype "passive"))
    )
    (net (code "148") (name "unconnected-(MP1-SHIELD-PadS41)") (class "Default")
      (node (ref "MP1") (pin "S41") (pinfunction "SHIELD_S41") (pintype "passive"))
    )
    (net (code "149") (name "unconnected-(MP1-SHIELD-PadS42)") (class "Default")
      (node (ref "MP1") (pin "S42") (pinfunction "SHIELD_S42") (pintype "passive"))
    )
    (net (code "150") (name "unconnected-(MP1-SHIELD-PadS43)") (class "Default")
      (node (ref "MP1") (pin "S43") (pinfunction "SHIELD_S43") (pintype "passive"))
    )
    (net (code "151") (name "unconnected-(MP1-SHIELD-PadS44)") (class "Default")
      (node (ref "MP1") (pin "S44") (pinfunction "SHIELD_S44") (pintype "passive"))
    )
    (net (code "152") (name "unconnected-(MP1-SHIELD-PadS45)") (class "Default")
      (node (ref "MP1") (pin "S45") (pinfunction "SHIELD_S45") (pintype "passive"))
    )
    (net (code "153") (name "unconnected-(MP1-SHIELD-PadS46)") (class "Default")
      (node (ref "MP1") (pin "S46") (pinfunction "SHIELD_S46") (pintype "passive"))
    )
    (net (code "154") (name "unconnected-(MP1-SHIELD-PadS47)") (class "Default")
      (node (ref "MP1") (pin "S47") (pinfunction "SHIELD_S47") (pintype "passive"))
    )
    (net (code "155") (name "unconnected-(U1A-PA1-Pad35)") (class "Default")
      (node (ref "U1") (pin "35") (pinfunction "PA1_35") (pintype "bidirectional"))
    )
    (net (code "156") (name "unconnected-(U1A-PA8-Pad100)") (class "Default")
      (node (ref "U1") (pin "100") (pinfunction "PA8_100") (pintype "bidirectional"))
    )
    (net (code "157") (name "unconnected-(U1A-PA11-Pad103)") (class "Default")
      (node (ref "U1") (pin "103") (pinfunction "PA11_103") (pintype "bidirectional"))
    )
    (net (code "158") (name "unconnected-(U1A-PA12-Pad104)") (class "Default")
      (node (ref "U1") (pin "104") (pinfunction "PA12_104") (pintype "bidirectional"))
    )
    (net (code "159") (name "unconnected-(U1A-PA15-Pad110)") (class "Default")
      (node (ref "U1") (pin "110") (pinfunction "PA15_110") (pintype "bidirectional"))
    )
    (net (code "160") (name "unconnected-(U1B-PB0-Pad46)") (class "Default")
      (node (ref "U1") (pin "46") (pinfunction "PB0_46") (pintype "bidirectional"))
    )
    (net (code "161") (name "unconnected-(U1B-PB1-Pad47)") (class "Default")
      (node (ref "U1") (pin "47") (pinfunction "PB1_47") (pintype "bidirectional"))
    )
    (net (code "162") (name "unconnected-(U1B-PB4-Pad134)") (class "Default")
      (node (ref "U1") (pin "134") (pinfunction "PB4_134") (pintype "bidirectional"))
    )
    (net (code "163") (name "unconnected-(U1B-PB11-Pad70)") (class "Default")
      (node (ref "U1") (pin "70") (pinfunction "PB11_70") (pintype "bidirectional"))
    )
    (net (code "164") (name "unconnected-(U1B-PB12-Pad73)") (class "Default")
      (node (ref "U1") (pin "73") (pinfunction "PB12_73") (pintype "bidirectional"))
    )
    (net (code "165") (name "unconnected-(U1B-PB13-Pad74)") (class "Default")
      (node (ref "U1") (pin "74") (pinfunction "PB13_74") (pintype "bidirectional"))
    )
    (net (code "166") (name "unconnected-(U1C-PD0-Pad114)") (class "Default")
      (node (ref "U1") (pin "114") (pinfunction "PD0_114") (pintype "bidirectional"))
    )
    (net (code "167") (name "unconnected-(U1C-PD1-Pad115)") (class "Default")
      (node (ref "U1") (pin "115") (pinfunction "PD1_115") (pintype "bidirectional"))
    )
    (net (code "168") (name "unconnected-(U1C-PD2-Pad116)") (class "Default")
      (node (ref "U1") (pin "116") (pinfunction "PD2_116") (pintype "bidirectional"))
    )
    (net (code "169") (name "unconnected-(U1C-PD3-Pad117)") (class "Default")
      (node (ref "U1") (pin "117") (pinfunction "PD3_117") (pintype "bidirectional"))
    )
    (net (code "170") (name "unconnected-(U1C-PD4-Pad118)") (class "Default")
      (node (ref "U1") (pin "118") (pinfunction "PD4_118") (pintype "bidirectional"))
    )
    (net (code "171") (name "unconnected-(U1C-PD5-Pad119)") (class "Default")
      (node (ref "U1") (pin "119") (pinfunction "PD5_119") (pintype "bidirectional"))
    )
    (net (code "172") (name "unconnected-(U1C-PD6-Pad122)") (class "Default")
      (node (ref "U1") (pin "122") (pinfunction "PD6_122") (pintype "bidirectional"))
    )
    (net (code "173") (name "unconnected-(U1C-PD7-Pad123)") (class "Default")
      (node (ref "U1") (pin "123") (pinfunction "PD7_123") (pintype "bidirectional"))
    )
    (net (code "174") (name "unconnected-(U1C-PD10-Pad79)") (class "Default")
      (node (ref "U1") (pin "79") (pinfunction "PD10_79") (pintype "bidirectional"))
    )
    (net (code "175") (name "unconnected-(U1C-PD11-Pad80)") (class "Default")
      (node (ref "U1") (pin "80") (pinfunction "PD11_80") (pintype "bidirectional"))
    )
    (net (code "176") (name "unconnected-(U1C-PD12-Pad81)") (class "Default")
      (node (ref "U1") (pin "81") (pinfunction "PD12_81") (pintype "bidirectional"))
    )
    (net (code "177") (name "unconnected-(U1C-PD13-Pad82)") (class "Default")
      (node (ref "U1") (pin "82") (pinfunction "PD13_82") (pintype "bidirectional"))
    )
    (net (code "178") (name "unconnected-(U1C-PD14-Pad85)") (class "Default")
      (node (ref "U1") (pin "85") (pinfunction "PD14_85") (pintype "bidirectional"))
    )
    (net (code "179") (name "unconnected-(U1C-PD15-Pad86)") (class "Default")
      (node (ref "U1") (pin "86") (pinfunction "PD15_86") (pintype "bidirectional"))
    )
  )
)
